# Gamepad_IO.net
KiCad netlist of a schematic drawn in Altium Designer
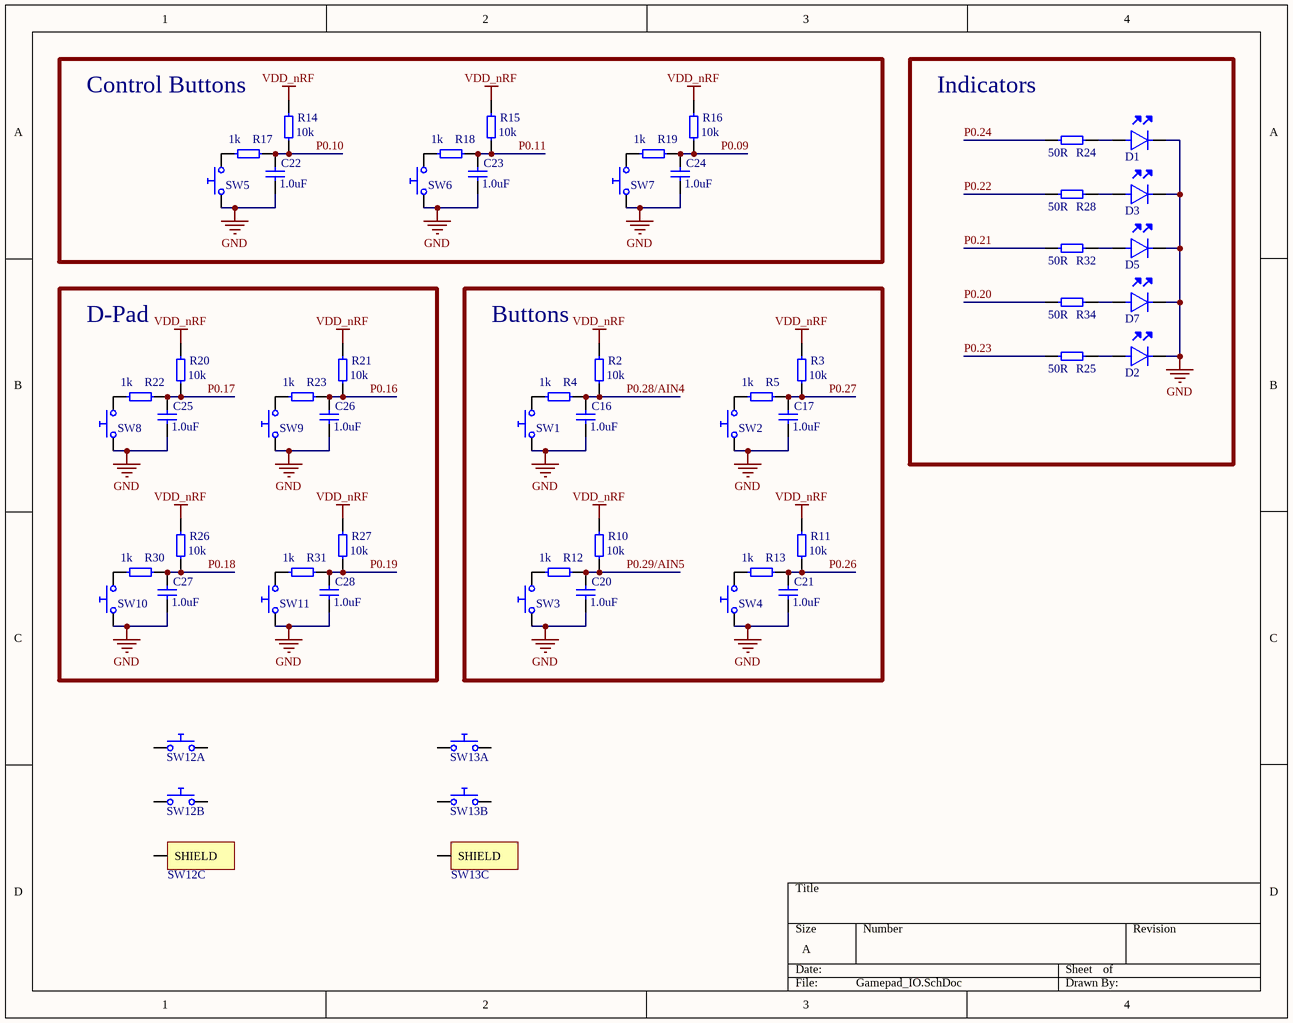
[diagram p0: Gamepad_IO.SchDoc]

(export (version "E")
  (design (tool "Eeschema 10.0.6"))
  (components
    (comp (ref "C16")
      (value "1.0uF")
      (footprint "0603 Capacitor")
      (libsource (lib "MoldsvorLibrary") (part "Capacitor"))
    )
    (comp (ref "C17")
      (value "1.0uF")
      (footprint "0603 Capacitor")
      (libsource (lib "MoldsvorLibrary") (part "Capacitor"))
    )
    (comp (ref "C20")
      (value "1.0uF")
      (footprint "0603 Capacitor")
      (libsource (lib "MoldsvorLibrary") (part "Capacitor"))
    )
    (comp (ref "C21")
      (value "1.0uF")
      (footprint "0603 Capacitor")
      (libsource (lib "MoldsvorLibrary") (part "Capacitor"))
    )
    (comp (ref "C22")
      (value "1.0uF")
      (footprint "0603 Capacitor")
      (libsource (lib "MoldsvorLibrary") (part "Capacitor"))
    )
    (comp (ref "C23")
      (value "1.0uF")
      (footprint "0603 Capacitor")
      (libsource (lib "MoldsvorLibrary") (part "Capacitor"))
    )
    (comp (ref "C24")
      (value "1.0uF")
      (footprint "0603 Capacitor")
      (libsource (lib "MoldsvorLibrary") (part "Capacitor"))
    )
    (comp (ref "C25")
      (value "1.0uF")
      (footprint "0603 Capacitor")
      (libsource (lib "MoldsvorLibrary") (part "Capacitor"))
    )
    (comp (ref "C26")
      (value "1.0uF")
      (footprint "0603 Capacitor")
      (libsource (lib "MoldsvorLibrary") (part "Capacitor"))
    )
    (comp (ref "C27")
      (value "1.0uF")
      (footprint "0603 Capacitor")
      (libsource (lib "MoldsvorLibrary") (part "Capacitor"))
    )
    (comp (ref "C28")
      (value "1.0uF")
      (footprint "0603 Capacitor")
      (libsource (lib "MoldsvorLibrary") (part "Capacitor"))
    )
    (comp (ref "D1") (value "LED") (footprint "0603 LED") (libsource (lib "MoldsvorLibrary") (part "LED")))
    (comp (ref "D2") (value "LED") (footprint "0603 LED") (libsource (lib "MoldsvorLibrary") (part "LED")))
    (comp (ref "D3") (value "LED") (footprint "0603 LED") (libsource (lib "MoldsvorLibrary") (part "LED")))
    (comp (ref "D5") (value "LED") (footprint "0603 LED") (libsource (lib "MoldsvorLibrary") (part "LED")))
    (comp (ref "D7") (value "LED") (footprint "0603 LED") (libsource (lib "MoldsvorLibrary") (part "LED")))
    (comp (ref "R2")
      (value "10k")
      (footprint "0603 Resistor")
      (libsource (lib "MoldsvorLibrary") (part "Resistor"))
    )
    (comp (ref "R3")
      (value "10k")
      (footprint "0603 Resistor")
      (libsource (lib "MoldsvorLibrary") (part "Resistor"))
    )
    (comp (ref "R4")
      (value "1k")
      (footprint "0603 Resistor")
      (libsource (lib "MoldsvorLibrary") (part "Resistor"))
    )
    (comp (ref "R5")
      (value "1k")
      (footprint "0603 Resistor")
      (libsource (lib "MoldsvorLibrary") (part "Resistor"))
    )
    (comp (ref "R10")
      (value "10k")
      (footprint "0603 Resistor")
      (libsource (lib "MoldsvorLibrary") (part "Resistor"))
    )
    (comp (ref "R11")
      (value "10k")
      (footprint "0603 Resistor")
      (libsource (lib "MoldsvorLibrary") (part "Resistor"))
    )
    (comp (ref "R12")
      (value "1k")
      (footprint "0603 Resistor")
      (libsource (lib "MoldsvorLibrary") (part "Resistor"))
    )
    (comp (ref "R13")
      (value "1k")
      (footprint "0603 Resistor")
      (libsource (lib "MoldsvorLibrary") (part "Resistor"))
    )
    (comp (ref "R14")
      (value "10k")
      (footprint "0603 Resistor")
      (libsource (lib "MoldsvorLibrary") (part "Resistor"))
    )
    (comp (ref "R15")
      (value "10k")
      (footprint "0603 Resistor")
      (libsource (lib "MoldsvorLibrary") (part "Resistor"))
    )
    (comp (ref "R16")
      (value "10k")
      (footprint "0603 Resistor")
      (libsource (lib "MoldsvorLibrary") (part "Resistor"))
    )
    (comp (ref "R17")
      (value "1k")
      (footprint "0603 Resistor")
      (libsource (lib "MoldsvorLibrary") (part "Resistor"))
    )
    (comp (ref "R18")
      (value "1k")
      (footprint "0603 Resistor")
      (libsource (lib "MoldsvorLibrary") (part "Resistor"))
    )
    (comp (ref "R19")
      (value "1k")
      (footprint "0603 Resistor")
      (libsource (lib "MoldsvorLibrary") (part "Resistor"))
    )
    (comp (ref "R20")
      (value "10k")
      (footprint "0603 Resistor")
      (libsource (lib "MoldsvorLibrary") (part "Resistor"))
    )
    (comp (ref "R21")
      (value "10k")
      (footprint "0603 Resistor")
      (libsource (lib "MoldsvorLibrary") (part "Resistor"))
    )
    (comp (ref "R22")
      (value "1k")
      (footprint "0603 Resistor")
      (libsource (lib "MoldsvorLibrary") (part "Resistor"))
    )
    (comp (ref "R23")
      (value "1k")
      (footprint "0603 Resistor")
      (libsource (lib "MoldsvorLibrary") (part "Resistor"))
    )
    (comp (ref "R24")
      (value "50R")
      (footprint "0603 Resistor")
      (libsource (lib "MoldsvorLibrary") (part "Resistor"))
    )
    (comp (ref "R25")
      (value "50R")
      (footprint "0603 Resistor")
      (libsource (lib "MoldsvorLibrary") (part "Resistor"))
    )
    (comp (ref "R26")
      (value "10k")
      (footprint "0603 Resistor")
      (libsource (lib "MoldsvorLibrary") (part "Resistor"))
    )
    (comp (ref "R27")
      (value "10k")
      (footprint "0603 Resistor")
      (libsource (lib "MoldsvorLibrary") (part "Resistor"))
    )
    (comp (ref "R28")
      (value "50R")
      (footprint "0603 Resistor")
      (libsource (lib "MoldsvorLibrary") (part "Resistor"))
    )
    (comp (ref "R30")
      (value "1k")
      (footprint "0603 Resistor")
      (libsource (lib "MoldsvorLibrary") (part "Resistor"))
    )
    (comp (ref "R31")
      (value "1k")
      (footprint "0603 Resistor")
      (libsource (lib "MoldsvorLibrary") (part "Resistor"))
    )
    (comp (ref "R32")
      (value "50R")
      (footprint "0603 Resistor")
      (libsource (lib "MoldsvorLibrary") (part "Resistor"))
    )
    (comp (ref "R34")
      (value "50R")
      (footprint "0603 Resistor")
      (libsource (lib "MoldsvorLibrary") (part "Resistor"))
    )
    (comp (ref "SW1")
      (value "Switch Button")
      (footprint "ButtonPad Version 1")
      (libsource (lib "Gamepad_Schematic_Library") (part "Switch Button"))
    )
    (comp (ref "SW2")
      (value "Switch Button")
      (footprint "ButtonPad Version 1")
      (libsource (lib "Gamepad_Schematic_Library") (part "Switch Button"))
    )
    (comp (ref "SW3")
      (value "Switch Button")
      (footprint "ButtonPad Version 1")
      (libsource (lib "Gamepad_Schematic_Library") (part "Switch Button"))
    )
    (comp (ref "SW4")
      (value "Switch Button")
      (footprint "ButtonPad Version 1")
      (libsource (lib "Gamepad_Schematic_Library") (part "Switch Button"))
    )
    (comp (ref "SW5")
      (value "Switch Button")
      (footprint "ButtonPad Version 1")
      (libsource (lib "Gamepad_Schematic_Library") (part "Switch Button"))
    )
    (comp (ref "SW6")
      (value "Switch Button")
      (footprint "ButtonPad Version 1")
      (libsource (lib "Gamepad_Schematic_Library") (part "Switch Button"))
    )
    (comp (ref "SW7")
      (value "Switch Button")
      (footprint "ButtonPad Version 1")
      (libsource (lib "Gamepad_Schematic_Library") (part "Switch Button"))
    )
    (comp (ref "SW8")
      (value "Switch Button")
      (footprint "ButtonPad Version 1")
      (libsource (lib "Gamepad_Schematic_Library") (part "Switch Button"))
    )
    (comp (ref "SW9")
      (value "Switch Button")
      (footprint "ButtonPad Version 1")
      (libsource (lib "Gamepad_Schematic_Library") (part "Switch Button"))
    )
    (comp (ref "SW10")
      (value "Switch Button")
      (footprint "ButtonPad Version 1")
      (libsource (lib "Gamepad_Schematic_Library") (part "Switch Button"))
    )
    (comp (ref "SW11")
      (value "Switch Button")
      (footprint "ButtonPad Version 1")
      (libsource (lib "Gamepad_Schematic_Library") (part "Switch Button"))
    )
    (comp (ref "SW12")
      (value "TL2243")
      (footprint "TL2243")
      (description "SWITCH TACTILE SPSTX2 0.05A 12V")
      (libsource (lib "Gamepad_Schematic_Library") (part "TL2243"))
    )
    (comp (ref "SW13")
      (value "TL2243")
      (footprint "TL2243")
      (description "SWITCH TACTILE SPSTX2 0.05A 12V")
      (libsource (lib "Gamepad_Schematic_Library") (part "TL2243"))
    )
  )
  (nets
    (net (code "1") (name "/P0.09") (class "Default")
      (node (ref "C24") (pin "2") (pinfunction "2_2") (pintype "passive"))
      (node (ref "R16") (pin "1") (pintype "passive"))
      (node (ref "R19") (pin "2") (pintype "passive"))
    )
    (net (code "2") (name "/P0.10") (class "Default")
      (node (ref "C22") (pin "2") (pinfunction "2_2") (pintype "passive"))
      (node (ref "R14") (pin "1") (pintype "passive"))
      (node (ref "R17") (pin "2") (pintype "passive"))
    )
    (net (code "3") (name "/P0.11") (class "Default")
      (node (ref "C23") (pin "2") (pinfunction "2_2") (pintype "passive"))
      (node (ref "R15") (pin "1") (pintype "passive"))
      (node (ref "R18") (pin "2") (pintype "passive"))
    )
    (net (code "4") (name "/P0.16") (class "Default")
      (node (ref "C26") (pin "2") (pinfunction "2_2") (pintype "passive"))
      (node (ref "R21") (pin "1") (pintype "passive"))
      (node (ref "R23") (pin "2") (pintype "passive"))
    )
    (net (code "5") (name "/P0.17") (class "Default")
      (node (ref "C25") (pin "2") (pinfunction "2_2") (pintype "passive"))
      (node (ref "R20") (pin "1") (pintype "passive"))
      (node (ref "R22") (pin "2") (pintype "passive"))
    )
    (net (code "6") (name "/P0.18") (class "Default")
      (node (ref "C27") (pin "2") (pinfunction "2_2") (pintype "passive"))
      (node (ref "R26") (pin "1") (pintype "passive"))
      (node (ref "R30") (pin "2") (pintype "passive"))
    )
    (net (code "7") (name "/P0.19") (class "Default")
      (node (ref "C28") (pin "2") (pinfunction "2_2") (pintype "passive"))
      (node (ref "R27") (pin "1") (pintype "passive"))
      (node (ref "R31") (pin "2") (pintype "passive"))
    )
    (net (code "8") (name "/P0.20") (class "Default") (node (ref "R34") (pin "1") (pintype "passive")))
    (net (code "9") (name "/P0.21") (class "Default") (node (ref "R32") (pin "1") (pintype "passive")))
    (net (code "10") (name "/P0.22") (class "Default") (node (ref "R28") (pin "1") (pintype "passive")))
    (net (code "11") (name "/P0.23") (class "Default") (node (ref "R25") (pin "1") (pintype "passive")))
    (net (code "12") (name "/P0.24") (class "Default") (node (ref "R24") (pin "1") (pintype "passive")))
    (net (code "13") (name "/P0.26") (class "Default")
      (node (ref "C21") (pin "2") (pinfunction "2_2") (pintype "passive"))
      (node (ref "R11") (pin "1") (pintype "passive"))
      (node (ref "R13") (pin "2") (pintype "passive"))
    )
    (net (code "14") (name "/P0.27") (class "Default")
      (node (ref "C17") (pin "2") (pinfunction "2_2") (pintype "passive"))
      (node (ref "R3") (pin "1") (pintype "passive"))
      (node (ref "R5") (pin "2") (pintype "passive"))
    )
    (net (code "15") (name "/P0.28{slash}AIN4") (class "Default")
      (node (ref "C16") (pin "2") (pinfunction "2_2") (pintype "passive"))
      (node (ref "R2") (pin "1") (pintype "passive"))
      (node (ref "R4") (pin "2") (pintype "passive"))
    )
    (net (code "16") (name "/P0.29{slash}AIN5") (class "Default")
      (node (ref "C20") (pin "2") (pinfunction "2_2") (pintype "passive"))
      (node (ref "R10") (pin "1") (pintype "passive"))
      (node (ref "R12") (pin "2") (pintype "passive"))
    )
    (net (code "17") (name "GND") (class "Default")
      (node (ref "C16") (pin "1") (pinfunction "1_1") (pintype "passive"))
      (node (ref "C17") (pin "1") (pinfunction "1_1") (pintype "passive"))
      (node (ref "C20") (pin "1") (pinfunction "1_1") (pintype "passive"))
      (node (ref "C21") (pin "1") (pinfunction "1_1") (pintype "passive"))
      (node (ref "C22") (pin "1") (pinfunction "1_1") (pintype "passive"))
      (node (ref "C23") (pin "1") (pinfunction "1_1") (pintype "passive"))
      (node (ref "C24") (pin "1") (pinfunction "1_1") (pintype "passive"))
      (node (ref "C25") (pin "1") (pinfunction "1_1") (pintype "passive"))
      (node (ref "C26") (pin "1") (pinfunction "1_1") (pintype "passive"))
      (node (ref "C27") (pin "1") (pinfunction "1_1") (pintype "passive"))
      (node (ref "C28") (pin "1") (pinfunction "1_1") (pintype "passive"))
      (node (ref "D1") (pin "2") (pintype "passive"))
      (node (ref "D2") (pin "2") (pintype "passive"))
      (node (ref "D3") (pin "2") (pintype "passive"))
      (node (ref "D5") (pin "2") (pintype "passive"))
      (node (ref "D7") (pin "2") (pintype "passive"))
      (node (ref "SW1") (pin "1") (pinfunction "1_1") (pintype "passive"))
      (node (ref "SW10") (pin "1") (pinfunction "1_1") (pintype "passive"))
      (node (ref "SW11") (pin "1") (pinfunction "1_1") (pintype "passive"))
      (node (ref "SW2") (pin "1") (pinfunction "1_1") (pintype "passive"))
      (node (ref "SW3") (pin "1") (pinfunction "1_1") (pintype "passive"))
      (node (ref "SW4") (pin "1") (pinfunction "1_1") (pintype "passive"))
      (node (ref "SW5") (pin "1") (pinfunction "1_1") (pintype "passive"))
      (node (ref "SW6") (pin "1") (pinfunction "1_1") (pintype "passive"))
      (node (ref "SW7") (pin "1") (pinfunction "1_1") (pintype "passive"))
      (node (ref "SW8") (pin "1") (pinfunction "1_1") (pintype "passive"))
      (node (ref "SW9") (pin "1") (pinfunction "1_1") (pintype "passive"))
    )
    (net (code "18") (name "Net-(D1-Pad1)") (class "Default")
      (node (ref "D1") (pin "1") (pintype "passive"))
      (node (ref "R24") (pin "2") (pintype "passive"))
    )
    (net (code "19") (name "Net-(D2-Pad1)") (class "Default")
      (node (ref "D2") (pin "1") (pintype "passive"))
      (node (ref "R25") (pin "2") (pintype "passive"))
    )
    (net (code "20") (name "Net-(D3-Pad1)") (class "Default")
      (node (ref "D3") (pin "1") (pintype "passive"))
      (node (ref "R28") (pin "2") (pintype "passive"))
    )
    (net (code "21") (name "Net-(D5-Pad1)") (class "Default")
      (node (ref "D5") (pin "1") (pintype "passive"))
      (node (ref "R32") (pin "2") (pintype "passive"))
    )
    (net (code "22") (name "Net-(D7-Pad1)") (class "Default")
      (node (ref "D7") (pin "1") (pintype "passive"))
      (node (ref "R34") (pin "2") (pintype "passive"))
    )
    (net (code "23") (name "Net-(R4-Pad1)") (class "Default")
      (node (ref "R4") (pin "1") (pintype "passive"))
      (node (ref "SW1") (pin "2") (pinfunction "2_2") (pintype "passive"))
    )
    (net (code "24") (name "Net-(R5-Pad1)") (class "Default")
      (node (ref "R5") (pin "1") (pintype "passive"))
      (node (ref "SW2") (pin "2") (pinfunction "2_2") (pintype "passive"))
    )
    (net (code "25") (name "Net-(R12-Pad1)") (class "Default")
      (node (ref "R12") (pin "1") (pintype "passive"))
      (node (ref "SW3") (pin "2") (pinfunction "2_2") (pintype "passive"))
    )
    (net (code "26") (name "Net-(R13-Pad1)") (class "Default")
      (node (ref "R13") (pin "1") (pintype "passive"))
      (node (ref "SW4") (pin "2") (pinfunction "2_2") (pintype "passive"))
    )
    (net (code "27") (name "Net-(R17-Pad1)") (class "Default")
      (node (ref "R17") (pin "1") (pintype "passive"))
      (node (ref "SW5") (pin "2") (pinfunction "2_2") (pintype "passive"))
    )
    (net (code "28") (name "Net-(R18-Pad1)") (class "Default")
      (node (ref "R18") (pin "1") (pintype "passive"))
      (node (ref "SW6") (pin "2") (pinfunction "2_2") (pintype "passive"))
    )
    (net (code "29") (name "Net-(R19-Pad1)") (class "Default")
      (node (ref "R19") (pin "1") (pintype "passive"))
      (node (ref "SW7") (pin "2") (pinfunction "2_2") (pintype "passive"))
    )
    (net (code "30") (name "Net-(R22-Pad1)") (class "Default")
      (node (ref "R22") (pin "1") (pintype "passive"))
      (node (ref "SW8") (pin "2") (pinfunction "2_2") (pintype "passive"))
    )
    (net (code "31") (name "Net-(R23-Pad1)") (class "Default")
      (node (ref "R23") (pin "1") (pintype "passive"))
      (node (ref "SW9") (pin "2") (pinfunction "2_2") (pintype "passive"))
    )
    (net (code "32") (name "Net-(R30-Pad1)") (class "Default")
      (node (ref "R30") (pin "1") (pintype "passive"))
      (node (ref "SW10") (pin "2") (pinfunction "2_2") (pintype "passive"))
    )
    (net (code "33") (name "Net-(R31-Pad1)") (class "Default")
      (node (ref "R31") (pin "1") (pintype "passive"))
      (node (ref "SW11") (pin "2") (pinfunction "2_2") (pintype "passive"))
    )
    (net (code "34") (name "VDD_nRF") (class "Default")
      (node (ref "R10") (pin "2") (pintype "passive"))
      (node (ref "R11") (pin "2") (pintype "passive"))
      (node (ref "R14") (pin "2") (pintype "passive"))
      (node (ref "R15") (pin "2") (pintype "passive"))
      (node (ref "R16") (pin "2") (pintype "passive"))
      (node (ref "R2") (pin "2") (pintype "passive"))
      (node (ref "R20") (pin "2") (pintype "passive"))
      (node (ref "R21") (pin "2") (pintype "passive"))
      (node (ref "R26") (pin "2") (pintype "passive"))
      (node (ref "R27") (pin "2") (pintype "passive"))
      (node (ref "R3") (pin "2") (pintype "passive"))
    )
    (net (code "35") (name "unconnected-(SW12-Pad1)") (class "Default")
      (node (ref "SW12") (pin "1") (pinfunction "1_1") (pintype "passive"))
    )
    (net (code "36") (name "unconnected-(SW12-Pad2)") (class "Default")
      (node (ref "SW12") (pin "2") (pinfunction "2_2") (pintype "passive"))
    )
    (net (code "37") (name "unconnected-(SW12-Pad3)") (class "Default")
      (node (ref "SW12") (pin "3") (pinfunction "3_3") (pintype "passive"))
    )
    (net (code "38") (name "unconnected-(SW12-Pad4)") (class "Default")
      (node (ref "SW12") (pin "4") (pinfunction "4_4") (pintype "passive"))
    )
    (net (code "39") (name "unconnected-(SW12-PadSHIELD)") (class "Default")
      (node (ref "SW12") (pin "SHIELD") (pinfunction "SHIELD_SHIELD") (pintype "passive"))
    )
    (net (code "40") (name "unconnected-(SW13-Pad1)") (class "Default")
      (node (ref "SW13") (pin "1") (pinfunction "1_1") (pintype "passive"))
    )
    (net (code "41") (name "unconnected-(SW13-Pad2)") (class "Default")
      (node (ref "SW13") (pin "2") (pinfunction "2_2") (pintype "passive"))
    )
    (net (code "42") (name "unconnected-(SW13-Pad3)") (class "Default")
      (node (ref "SW13") (pin "3") (pinfunction "3_3") (pintype "passive"))
    )
    (net (code "43") (name "unconnected-(SW13-Pad4)") (class "Default")
      (node (ref "SW13") (pin "4") (pinfunction "4_4") (pintype "passive"))
    )
    (net (code "44") (name "unconnected-(SW13-PadSHIELD)") (class "Default")
      (node (ref "SW13") (pin "SHIELD") (pinfunction "SHIELD_SHIELD") (pintype "passive"))
    )
  )
)
